# photodiodes-board.net
KiCad netlist of a schematic drawn in EAGLE
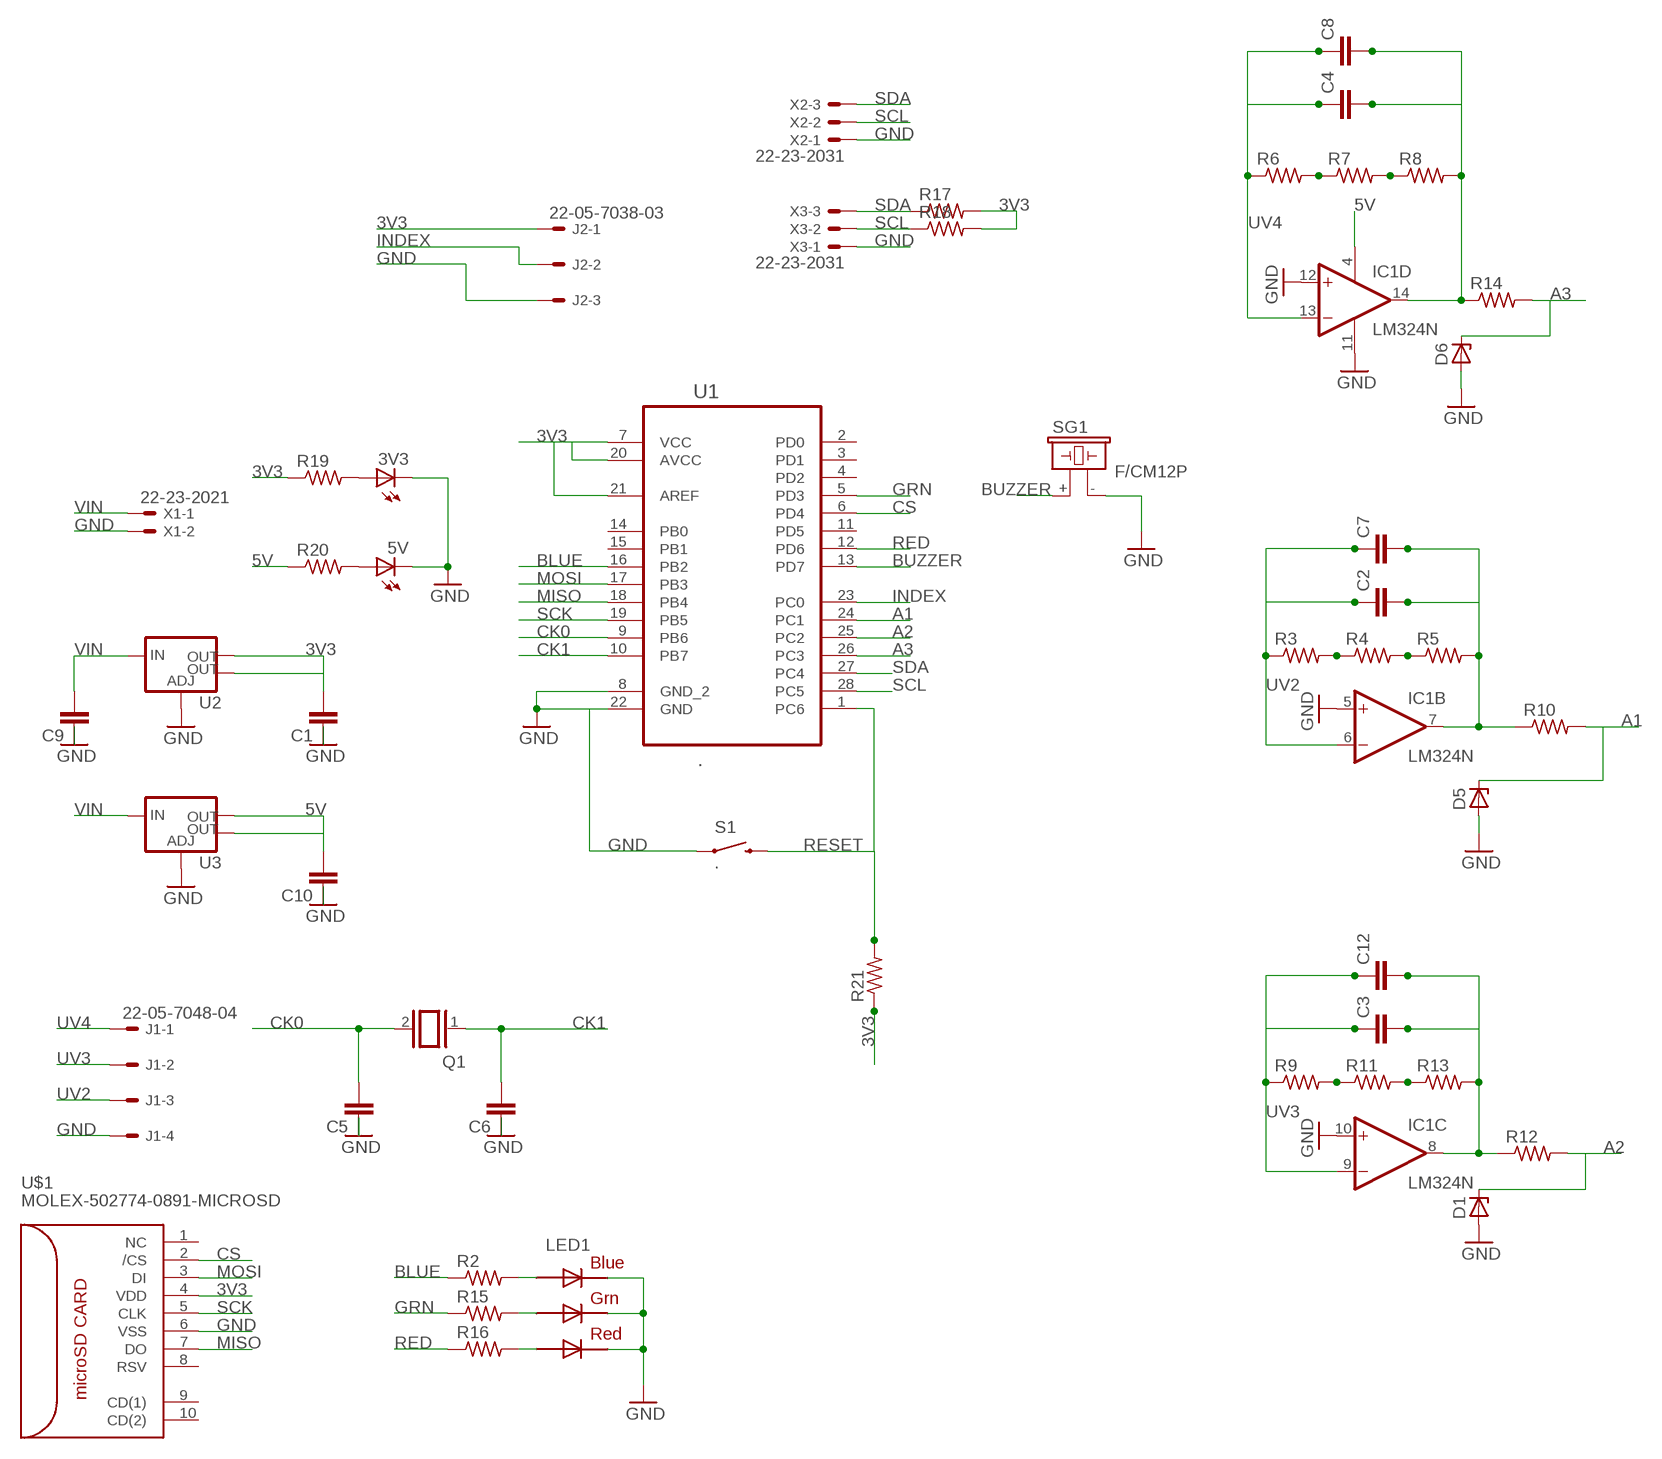
[diagram p0: schematic, sheet 1]

(export (version "E")
  (design (tool "Eeschema 10.0.6"))
  (components
    (comp (ref "3V3")
      (value "LEDSMT1206")
      (footprint "eagle-import:1206")
      (libsource (lib "eagle-import") (part "LEDSMT1206"))
    )
    (comp (ref "5V")
      (value "LEDSMT1206")
      (footprint "eagle-import:1206")
      (libsource (lib "eagle-import") (part "LEDSMT1206"))
    )
    (comp (ref "C1")
      (value "10UF-1210-50V-20%")
      (footprint "eagle-import:1210")
      (libsource (lib "eagle-import") (part "10UF-1210-50V-20%"))
    )
    (comp (ref "C2")
      (value "10UF-1210-50V-20%")
      (footprint "eagle-import:1210")
      (libsource (lib "eagle-import") (part "10UF-1210-50V-20%"))
    )
    (comp (ref "C3")
      (value "10UF-1210-50V-20%")
      (footprint "eagle-import:1210")
      (libsource (lib "eagle-import") (part "10UF-1210-50V-20%"))
    )
    (comp (ref "C4")
      (value "10UF-1210-50V-20%")
      (footprint "eagle-import:1210")
      (libsource (lib "eagle-import") (part "10UF-1210-50V-20%"))
    )
    (comp (ref "C5")
      (value "10UF-1210-50V-20%")
      (footprint "eagle-import:1210")
      (libsource (lib "eagle-import") (part "10UF-1210-50V-20%"))
    )
    (comp (ref "C6")
      (value "10UF-1210-50V-20%")
      (footprint "eagle-import:1210")
      (libsource (lib "eagle-import") (part "10UF-1210-50V-20%"))
    )
    (comp (ref "C7")
      (value "10UF-1210-50V-20%")
      (footprint "eagle-import:1210")
      (libsource (lib "eagle-import") (part "10UF-1210-50V-20%"))
    )
    (comp (ref "C8")
      (value "10UF-1210-50V-20%")
      (footprint "eagle-import:1210")
      (libsource (lib "eagle-import") (part "10UF-1210-50V-20%"))
    )
    (comp (ref "C9")
      (value "10UF-1210-50V-20%")
      (footprint "eagle-import:1210")
      (libsource (lib "eagle-import") (part "10UF-1210-50V-20%"))
    )
    (comp (ref "C10")
      (value "10UF-1210-50V-20%")
      (footprint "eagle-import:1210")
      (libsource (lib "eagle-import") (part "10UF-1210-50V-20%"))
    )
    (comp (ref "C12")
      (value "10UF-1210-50V-20%")
      (footprint "eagle-import:1210")
      (libsource (lib "eagle-import") (part "10UF-1210-50V-20%"))
    )
    (comp (ref "D1")
      (value "ZENER-DIODEZD-12.5")
      (footprint "eagle-import:ZDIO12.5")
      (libsource (lib "eagle-import") (part "ZENER-DIODEZD-12.5"))
    )
    (comp (ref "D5")
      (value "ZENER-DIODEZD-12.5")
      (footprint "eagle-import:ZDIO12.5")
      (libsource (lib "eagle-import") (part "ZENER-DIODEZD-12.5"))
    )
    (comp (ref "D6")
      (value "ZENER-DIODEZD-12.5")
      (footprint "eagle-import:ZDIO12.5")
      (libsource (lib "eagle-import") (part "ZENER-DIODEZD-12.5"))
    )
    (comp (ref "IC1")
      (value "LM324N")
      (footprint "eagle-import:DIL14")
      (libsource (lib "eagle-import") (part "LM324N"))
    )
    (comp (ref "J1")
      (value "22-05-7048-04")
      (footprint "eagle-import:7395-04")
      (libsource (lib "eagle-import") (part "22-?-0405-7048"))
    )
    (comp (ref "J2")
      (value "22-05-7038-03")
      (footprint "eagle-import:7395-03")
      (libsource (lib "eagle-import") (part "22-?-0305-7038"))
    )
    (comp (ref "LED1")
      (value ".")
      (footprint "eagle-import:RGBLED5050")
      (libsource (lib "eagle-import") (part "RGBLED5050"))
    )
    (comp (ref "Q1")
      (value "XTAL/S")
      (footprint "eagle-import:QS")
      (libsource (lib "eagle-import") (part "XTAL/S"))
    )
    (comp (ref "R2")
      (value "R-US_M1206")
      (footprint "eagle-import:M1206")
      (libsource (lib "eagle-import") (part "R-US_M1206"))
    )
    (comp (ref "R3")
      (value "R-US_0207/12")
      (footprint "eagle-import:0207_12")
      (libsource (lib "eagle-import") (part "R-US_0207/12"))
    )
    (comp (ref "R4")
      (value "R-US_0207/12")
      (footprint "eagle-import:0207_12")
      (libsource (lib "eagle-import") (part "R-US_0207/12"))
    )
    (comp (ref "R5")
      (value "R-US_0207/12")
      (footprint "eagle-import:0207_12")
      (libsource (lib "eagle-import") (part "R-US_0207/12"))
    )
    (comp (ref "R6")
      (value "R-US_0207/12")
      (footprint "eagle-import:0207_12")
      (libsource (lib "eagle-import") (part "R-US_0207/12"))
    )
    (comp (ref "R7")
      (value "R-US_0207/12")
      (footprint "eagle-import:0207_12")
      (libsource (lib "eagle-import") (part "R-US_0207/12"))
    )
    (comp (ref "R8")
      (value "R-US_0207/12")
      (footprint "eagle-import:0207_12")
      (libsource (lib "eagle-import") (part "R-US_0207/12"))
    )
    (comp (ref "R9")
      (value "R-US_0207/12")
      (footprint "eagle-import:0207_12")
      (libsource (lib "eagle-import") (part "R-US_0207/12"))
    )
    (comp (ref "R10")
      (value "R-US_M1206")
      (footprint "eagle-import:M1206")
      (libsource (lib "eagle-import") (part "R-US_M1206"))
    )
    (comp (ref "R11")
      (value "R-US_0207/12")
      (footprint "eagle-import:0207_12")
      (libsource (lib "eagle-import") (part "R-US_0207/12"))
    )
    (comp (ref "R12")
      (value "R-US_M1206")
      (footprint "eagle-import:M1206")
      (libsource (lib "eagle-import") (part "R-US_M1206"))
    )
    (comp (ref "R13")
      (value "R-US_0207/12")
      (footprint "eagle-import:0207_12")
      (libsource (lib "eagle-import") (part "R-US_0207/12"))
    )
    (comp (ref "R14")
      (value "R-US_M1206")
      (footprint "eagle-import:M1206")
      (libsource (lib "eagle-import") (part "R-US_M1206"))
    )
    (comp (ref "R15")
      (value "R-US_M1206")
      (footprint "eagle-import:M1206")
      (libsource (lib "eagle-import") (part "R-US_M1206"))
    )
    (comp (ref "R16")
      (value "R-US_M1206")
      (footprint "eagle-import:M1206")
      (libsource (lib "eagle-import") (part "R-US_M1206"))
    )
    (comp (ref "R17")
      (value "R-US_M1206")
      (footprint "eagle-import:M1206")
      (libsource (lib "eagle-import") (part "R-US_M1206"))
    )
    (comp (ref "R18")
      (value "R-US_M1206")
      (footprint "eagle-import:M1206")
      (libsource (lib "eagle-import") (part "R-US_M1206"))
    )
    (comp (ref "R19")
      (value "R-US_M1206")
      (footprint "eagle-import:M1206")
      (libsource (lib "eagle-import") (part "R-US_M1206"))
    )
    (comp (ref "R20")
      (value "R-US_M1206")
      (footprint "eagle-import:M1206")
      (libsource (lib "eagle-import") (part "R-US_M1206"))
    )
    (comp (ref "R21")
      (value "R-US_M1206")
      (footprint "eagle-import:M1206")
      (libsource (lib "eagle-import") (part "R-US_M1206"))
    )
    (comp (ref "S1")
      (value ".")
      (footprint "eagle-import:TACTILE-SWITCH-1101NE")
      (libsource (lib "eagle-import") (part "SWITCH-MOMENTARY-2SMD-1101NE"))
    )
    (comp (ref "SG1")
      (value "F/CM12P")
      (footprint "eagle-import:F_CM12P")
      (libsource (lib "eagle-import") (part "F/CM12P"))
    )
    (comp (ref "U$1")
      (value "MOLEX-502774-0891-MICROSD")
      (footprint "eagle-import:MOLEX-502774-0891-MICROSD")
      (libsource (lib "eagle-import") (part "MOLEX-502774-0891-MICROSD"))
    )
    (comp (ref "U1")
      (value ".")
      (footprint "eagle-import:DIP254P762X457-28")
      (fields (field (name "MPN") "ATMEGA328P-PU"))
      (libsource (lib "eagle-import") (part "ATMEGA328P-PU"))
    )
    (comp (ref "U2")
      (value "V_REG_LM1117SOT223")
      (footprint "eagle-import:SOT223")
      (libsource (lib "eagle-import") (part "V_REG_LM1117SOT223"))
    )
    (comp (ref "U3")
      (value "V_REG_LM1117SOT223")
      (footprint "eagle-import:SOT223")
      (libsource (lib "eagle-import") (part "V_REG_LM1117SOT223"))
    )
    (comp (ref "X1")
      (value "22-23-2021")
      (footprint "eagle-import:22-23-2021")
      (fields (field (name "MF") "MOLEX"))
      (libsource (lib "eagle-import") (part "22-23-2021"))
    )
    (comp (ref "X2")
      (value "22-23-2031")
      (footprint "eagle-import:22-23-2031")
      (fields (field (name "MF") "MOLEX"))
      (libsource (lib "eagle-import") (part "22-23-2031"))
    )
    (comp (ref "X3")
      (value "22-23-2031")
      (footprint "eagle-import:22-23-2031")
      (fields (field (name "MF") "MOLEX"))
      (libsource (lib "eagle-import") (part "22-23-2031"))
    )
  )
  (nets
    (net (code "1") (name "/3V3") (class "Default")
      (node (ref "C1") (pin "2") (pinfunction "2_2") (pintype "passive"))
      (node (ref "J2") (pin "1") (pinfunction "S_1") (pintype "passive"))
      (node (ref "R17") (pin "2") (pinfunction "2_2") (pintype "passive"))
      (node (ref "R18") (pin "2") (pinfunction "2_2") (pintype "passive"))
      (node (ref "R19") (pin "1") (pinfunction "1_1") (pintype "passive"))
      (node (ref "R21") (pin "1") (pinfunction "1_1") (pintype "passive"))
      (node (ref "U$1") (pin "4") (pinfunction "VDD_4") (pintype "bidirectional"))
      (node (ref "U1") (pin "20") (pinfunction "AVCC_20") (pintype "power_in"))
      (node (ref "U1") (pin "21") (pinfunction "AREF_21") (pintype "input"))
      (node (ref "U1") (pin "7") (pinfunction "VCC_7") (pintype "power_in"))
      (node (ref "U2") (pin "2") (pinfunction "OUT_2") (pintype "output"))
      (node (ref "U2") (pin "4") (pinfunction "OUT_4") (pintype "output"))
    )
    (net (code "2") (name "/5V") (class "Default")
      (node (ref "C10") (pin "2") (pinfunction "2_2") (pintype "passive"))
      (node (ref "IC1") (pin "4") (pinfunction "V+_4") (pintype "power_in"))
      (node (ref "R20") (pin "1") (pinfunction "1_1") (pintype "passive"))
      (node (ref "U3") (pin "2") (pinfunction "OUT_2") (pintype "output"))
      (node (ref "U3") (pin "4") (pinfunction "OUT_4") (pintype "output"))
    )
    (net (code "3") (name "/A1") (class "Default")
      (node (ref "D5") (pin "C") (pinfunction "C_C") (pintype "passive"))
      (node (ref "R10") (pin "2") (pinfunction "2_2") (pintype "passive"))
      (node (ref "U1") (pin "24") (pinfunction "PC1_24") (pintype "bidirectional"))
    )
    (net (code "4") (name "/A2") (class "Default")
      (node (ref "D1") (pin "C") (pinfunction "C_C") (pintype "passive"))
      (node (ref "R12") (pin "2") (pinfunction "2_2") (pintype "passive"))
      (node (ref "U1") (pin "25") (pinfunction "PC2_25") (pintype "bidirectional"))
    )
    (net (code "5") (name "/A3") (class "Default")
      (node (ref "D6") (pin "C") (pinfunction "C_C") (pintype "passive"))
      (node (ref "R14") (pin "2") (pinfunction "2_2") (pintype "passive"))
      (node (ref "U1") (pin "26") (pinfunction "PC3_26") (pintype "bidirectional"))
    )
    (net (code "6") (name "/BLUE") (class "Default")
      (node (ref "R2") (pin "1") (pinfunction "1_1") (pintype "passive"))
      (node (ref "U1") (pin "16") (pinfunction "PB2_16") (pintype "bidirectional"))
    )
    (net (code "7") (name "/BUZZER") (class "Default")
      (node (ref "SG1") (pin "+") (pinfunction "1_+") (pintype "passive"))
      (node (ref "U1") (pin "13") (pinfunction "PD7_13") (pintype "bidirectional"))
    )
    (net (code "8") (name "/CK0") (class "Default")
      (node (ref "C5") (pin "2") (pinfunction "2_2") (pintype "passive"))
      (node (ref "Q1") (pin "2") (pinfunction "2_2") (pintype "passive"))
      (node (ref "U1") (pin "9") (pinfunction "PB6_9") (pintype "bidirectional"))
    )
    (net (code "9") (name "/CK1") (class "Default")
      (node (ref "C6") (pin "2") (pinfunction "2_2") (pintype "passive"))
      (node (ref "Q1") (pin "1") (pinfunction "1_1") (pintype "passive"))
      (node (ref "U1") (pin "10") (pinfunction "PB7_10") (pintype "bidirectional"))
    )
    (net (code "10") (name "/CS") (class "Default")
      (node (ref "U$1") (pin "2") (pinfunction "/CS_2") (pintype "bidirectional"))
      (node (ref "U1") (pin "6") (pinfunction "PD4_6") (pintype "bidirectional"))
    )
    (net (code "11") (name "/GRN") (class "Default")
      (node (ref "R15") (pin "1") (pinfunction "1_1") (pintype "passive"))
      (node (ref "U1") (pin "5") (pinfunction "PD3_5") (pintype "bidirectional"))
    )
    (net (code "12") (name "/INDEX") (class "Default")
      (node (ref "J2") (pin "2") (pinfunction "S_2") (pintype "passive"))
      (node (ref "U1") (pin "23") (pinfunction "PC0_23") (pintype "bidirectional"))
    )
    (net (code "13") (name "/MISO") (class "Default")
      (node (ref "U$1") (pin "7") (pinfunction "DO_7") (pintype "bidirectional"))
      (node (ref "U1") (pin "18") (pinfunction "PB4_18") (pintype "bidirectional"))
    )
    (net (code "14") (name "/MOSI") (class "Default")
      (node (ref "U$1") (pin "3") (pinfunction "DI_3") (pintype "bidirectional"))
      (node (ref "U1") (pin "17") (pinfunction "PB3_17") (pintype "bidirectional"))
    )
    (net (code "15") (name "/N$15") (class "Default")
      (node (ref "C4") (pin "2") (pinfunction "2_2") (pintype "passive"))
      (node (ref "C8") (pin "2") (pinfunction "2_2") (pintype "passive"))
      (node (ref "IC1") (pin "14") (pinfunction "OUT_14") (pintype "output"))
      (node (ref "R14") (pin "1") (pinfunction "1_1") (pintype "passive"))
      (node (ref "R8") (pin "2") (pinfunction "2_2") (pintype "passive"))
    )
    (net (code "16") (name "/N$20") (class "Default")
      (node (ref "C12") (pin "2") (pinfunction "2_2") (pintype "passive"))
      (node (ref "C3") (pin "2") (pinfunction "2_2") (pintype "passive"))
      (node (ref "IC1") (pin "8") (pinfunction "OUT_8") (pintype "output"))
      (node (ref "R12") (pin "1") (pinfunction "1_1") (pintype "passive"))
      (node (ref "R13") (pin "2") (pinfunction "2_2") (pintype "passive"))
    )
    (net (code "17") (name "/N$28") (class "Default")
      (node (ref "C2") (pin "2") (pinfunction "2_2") (pintype "passive"))
      (node (ref "C7") (pin "2") (pinfunction "2_2") (pintype "passive"))
      (node (ref "IC1") (pin "7") (pinfunction "OUT_7") (pintype "output"))
      (node (ref "R10") (pin "1") (pinfunction "1_1") (pintype "passive"))
      (node (ref "R5") (pin "2") (pinfunction "2_2") (pintype "passive"))
    )
    (net (code "18") (name "/RED") (class "Default")
      (node (ref "R16") (pin "1") (pinfunction "1_1") (pintype "passive"))
      (node (ref "U1") (pin "12") (pinfunction "PD6_12") (pintype "bidirectional"))
    )
    (net (code "19") (name "/RESET") (class "Default")
      (node (ref "R21") (pin "2") (pinfunction "2_2") (pintype "passive"))
      (node (ref "S1") (pin "2") (pinfunction "2_2") (pintype "passive"))
      (node (ref "U1") (pin "1") (pinfunction "PC6_1") (pintype "bidirectional"))
    )
    (net (code "20") (name "/SCK") (class "Default")
      (node (ref "U$1") (pin "5") (pinfunction "CLK_5") (pintype "bidirectional"))
      (node (ref "U1") (pin "19") (pinfunction "PB5_19") (pintype "bidirectional"))
    )
    (net (code "21") (name "/SCL") (class "Default")
      (node (ref "R18") (pin "1") (pinfunction "1_1") (pintype "passive"))
      (node (ref "U1") (pin "28") (pinfunction "PC5_28") (pintype "bidirectional"))
      (node (ref "X2") (pin "2") (pinfunction "S_2") (pintype "passive"))
      (node (ref "X3") (pin "2") (pinfunction "S_2") (pintype "passive"))
    )
    (net (code "22") (name "/SDA") (class "Default")
      (node (ref "R17") (pin "1") (pinfunction "1_1") (pintype "passive"))
      (node (ref "U1") (pin "27") (pinfunction "PC4_27") (pintype "bidirectional"))
      (node (ref "X2") (pin "3") (pinfunction "S_3") (pintype "passive"))
      (node (ref "X3") (pin "3") (pinfunction "S_3") (pintype "passive"))
    )
    (net (code "23") (name "/UV2") (class "Default")
      (node (ref "C2") (pin "1") (pinfunction "1_1") (pintype "passive"))
      (node (ref "C7") (pin "1") (pinfunction "1_1") (pintype "passive"))
      (node (ref "IC1") (pin "6") (pinfunction "-IN_6") (pintype "input"))
      (node (ref "J1") (pin "3") (pinfunction "S_3") (pintype "passive"))
      (node (ref "R3") (pin "1") (pinfunction "1_1") (pintype "passive"))
    )
    (net (code "24") (name "/UV3") (class "Default")
      (node (ref "C12") (pin "1") (pinfunction "1_1") (pintype "passive"))
      (node (ref "C3") (pin "1") (pinfunction "1_1") (pintype "passive"))
      (node (ref "IC1") (pin "9") (pinfunction "-IN_9") (pintype "input"))
      (node (ref "J1") (pin "2") (pinfunction "S_2") (pintype "passive"))
      (node (ref "R9") (pin "1") (pinfunction "1_1") (pintype "passive"))
    )
    (net (code "25") (name "/UV4") (class "Default")
      (node (ref "C4") (pin "1") (pinfunction "1_1") (pintype "passive"))
      (node (ref "C8") (pin "1") (pinfunction "1_1") (pintype "passive"))
      (node (ref "IC1") (pin "13") (pinfunction "-IN_13") (pintype "input"))
      (node (ref "J1") (pin "1") (pinfunction "S_1") (pintype "passive"))
      (node (ref "R6") (pin "1") (pinfunction "1_1") (pintype "passive"))
    )
    (net (code "26") (name "/VIN") (class "Default")
      (node (ref "C9") (pin "2") (pinfunction "2_2") (pintype "passive"))
      (node (ref "U2") (pin "3") (pinfunction "IN_3") (pintype "input"))
      (node (ref "U3") (pin "3") (pinfunction "IN_3") (pintype "input"))
      (node (ref "X1") (pin "1") (pinfunction "S_1") (pintype "passive"))
    )
    (net (code "27") (name "GND") (class "Default")
      (node (ref "3V3") (pin "C") (pinfunction "C_C") (pintype "passive"))
      (node (ref "5V") (pin "C") (pinfunction "C_C") (pintype "passive"))
      (node (ref "C1") (pin "1") (pinfunction "1_1") (pintype "passive"))
      (node (ref "C10") (pin "1") (pinfunction "1_1") (pintype "passive"))
      (node (ref "C5") (pin "1") (pinfunction "1_1") (pintype "passive"))
      (node (ref "C6") (pin "1") (pinfunction "1_1") (pintype "passive"))
      (node (ref "C9") (pin "1") (pinfunction "1_1") (pintype "passive"))
      (node (ref "D1") (pin "A") (pinfunction "A_A") (pintype "passive"))
      (node (ref "D5") (pin "A") (pinfunction "A_A") (pintype "passive"))
      (node (ref "D6") (pin "A") (pinfunction "A_A") (pintype "passive"))
      (node (ref "IC1") (pin "10") (pinfunction "+IN_10") (pintype "input"))
      (node (ref "IC1") (pin "11") (pinfunction "V-_11") (pintype "power_in"))
      (node (ref "IC1") (pin "12") (pinfunction "+IN_12") (pintype "input"))
      (node (ref "IC1") (pin "5") (pinfunction "+IN_5") (pintype "input"))
      (node (ref "J1") (pin "4") (pinfunction "S_4") (pintype "passive"))
      (node (ref "J2") (pin "3") (pinfunction "S_3") (pintype "passive"))
      (node (ref "LED1") (pin "4") (pinfunction "BLUE_C_4") (pintype "bidirectional"))
      (node (ref "LED1") (pin "5") (pinfunction "RED_C_5") (pintype "bidirectional"))
      (node (ref "LED1") (pin "6") (pinfunction "GREEN_C_6") (pintype "bidirectional"))
      (node (ref "S1") (pin "1") (pinfunction "1_1") (pintype "passive"))
      (node (ref "SG1") (pin "-") (pinfunction "2_-") (pintype "passive"))
      (node (ref "U$1") (pin "6") (pinfunction "VSS_6") (pintype "bidirectional"))
      (node (ref "U1") (pin "22") (pinfunction "GND_22") (pintype "passive"))
      (node (ref "U1") (pin "8") (pinfunction "GND_2_8") (pintype "passive"))
      (node (ref "U2") (pin "1") (pinfunction "ADJ_1") (pintype "input"))
      (node (ref "U3") (pin "1") (pinfunction "ADJ_1") (pintype "input"))
      (node (ref "X1") (pin "2") (pinfunction "S_2") (pintype "passive"))
      (node (ref "X2") (pin "1") (pinfunction "S_1") (pintype "passive"))
      (node (ref "X3") (pin "1") (pinfunction "S_1") (pintype "passive"))
    )
    (net (code "28") (name "Net-(3V3-PadA)") (class "Default")
      (node (ref "3V3") (pin "A") (pinfunction "A_A") (pintype "passive"))
      (node (ref "R19") (pin "2") (pinfunction "2_2") (pintype "passive"))
    )
    (net (code "29") (name "Net-(5V-PadA)") (class "Default")
      (node (ref "5V") (pin "A") (pinfunction "A_A") (pintype "passive"))
      (node (ref "R20") (pin "2") (pinfunction "2_2") (pintype "passive"))
    )
    (net (code "30") (name "Net-(LED1-BLUE_A)") (class "Default")
      (node (ref "LED1") (pin "3") (pinfunction "BLUE_A_3") (pintype "bidirectional"))
      (node (ref "R2") (pin "2") (pinfunction "2_2") (pintype "passive"))
    )
    (net (code "31") (name "Net-(LED1-GREEN_A)") (class "Default")
      (node (ref "LED1") (pin "1") (pinfunction "GREEN_A_1") (pintype "bidirectional"))
      (node (ref "R15") (pin "2") (pinfunction "2_2") (pintype "passive"))
    )
    (net (code "32") (name "Net-(LED1-RED_A)") (class "Default")
      (node (ref "LED1") (pin "2") (pinfunction "RED_A_2") (pintype "bidirectional"))
      (node (ref "R16") (pin "2") (pinfunction "2_2") (pintype "passive"))
    )
    (net (code "33") (name "Net-(R3-Pad2)") (class "Default")
      (node (ref "R3") (pin "2") (pinfunction "2_2") (pintype "passive"))
      (node (ref "R4") (pin "1") (pinfunction "1_1") (pintype "passive"))
    )
    (net (code "34") (name "Net-(R4-Pad2)") (class "Default")
      (node (ref "R4") (pin "2") (pinfunction "2_2") (pintype "passive"))
      (node (ref "R5") (pin "1") (pinfunction "1_1") (pintype "passive"))
    )
    (net (code "35") (name "Net-(R6-Pad2)") (class "Default")
      (node (ref "R6") (pin "2") (pinfunction "2_2") (pintype "passive"))
      (node (ref "R7") (pin "1") (pinfunction "1_1") (pintype "passive"))
    )
    (net (code "36") (name "Net-(R7-Pad2)") (class "Default")
      (node (ref "R7") (pin "2") (pinfunction "2_2") (pintype "passive"))
      (node (ref "R8") (pin "1") (pinfunction "1_1") (pintype "passive"))
    )
    (net (code "37") (name "Net-(R11-Pad1)") (class "Default")
      (node (ref "R11") (pin "1") (pinfunction "1_1") (pintype "passive"))
      (node (ref "R9") (pin "2") (pinfunction "2_2") (pintype "passive"))
    )
    (net (code "38") (name "Net-(R11-Pad2)") (class "Default")
      (node (ref "R11") (pin "2") (pinfunction "2_2") (pintype "passive"))
      (node (ref "R13") (pin "1") (pinfunction "1_1") (pintype "passive"))
    )
    (net (code "39") (name "unconnected-(U$1-CD(1)-Pad9)") (class "Default")
      (node (ref "U$1") (pin "9") (pinfunction "CD(1)_9") (pintype "bidirectional"))
    )
    (net (code "40") (name "unconnected-(U$1-CD(2)-Pad10)") (class "Default")
      (node (ref "U$1") (pin "10") (pinfunction "CD(2)_10") (pintype "bidirectional"))
    )
    (net (code "41") (name "unconnected-(U$1-NC-Pad1)") (class "Default")
      (node (ref "U$1") (pin "1") (pinfunction "NC_1") (pintype "bidirectional"))
    )
    (net (code "42") (name "unconnected-(U$1-RSV-Pad8)") (class "Default")
      (node (ref "U$1") (pin "8") (pinfunction "RSV_8") (pintype "bidirectional"))
    )
    (net (code "43") (name "unconnected-(U1-PB0-Pad14)") (class "Default")
      (node (ref "U1") (pin "14") (pinfunction "PB0_14") (pintype "bidirectional"))
    )
    (net (code "44") (name "unconnected-(U1-PB1-Pad15)") (class "Default")
      (node (ref "U1") (pin "15") (pinfunction "PB1_15") (pintype "bidirectional"))
    )
    (net (code "45") (name "unconnected-(U1-PD0-Pad2)") (class "Default")
      (node (ref "U1") (pin "2") (pinfunction "PD0_2") (pintype "bidirectional"))
    )
    (net (code "46") (name "unconnected-(U1-PD1-Pad3)") (class "Default")
      (node (ref "U1") (pin "3") (pinfunction "PD1_3") (pintype "bidirectional"))
    )
    (net (code "47") (name "unconnected-(U1-PD2-Pad4)") (class "Default")
      (node (ref "U1") (pin "4") (pinfunction "PD2_4") (pintype "bidirectional"))
    )
    (net (code "48") (name "unconnected-(U1-PD5-Pad11)") (class "Default")
      (node (ref "U1") (pin "11") (pinfunction "PD5_11") (pintype "bidirectional"))
    )
  )
)
